# MB1-Hed-r1_0.net
KiCad netlist of a schematic drawn in Altium Designer
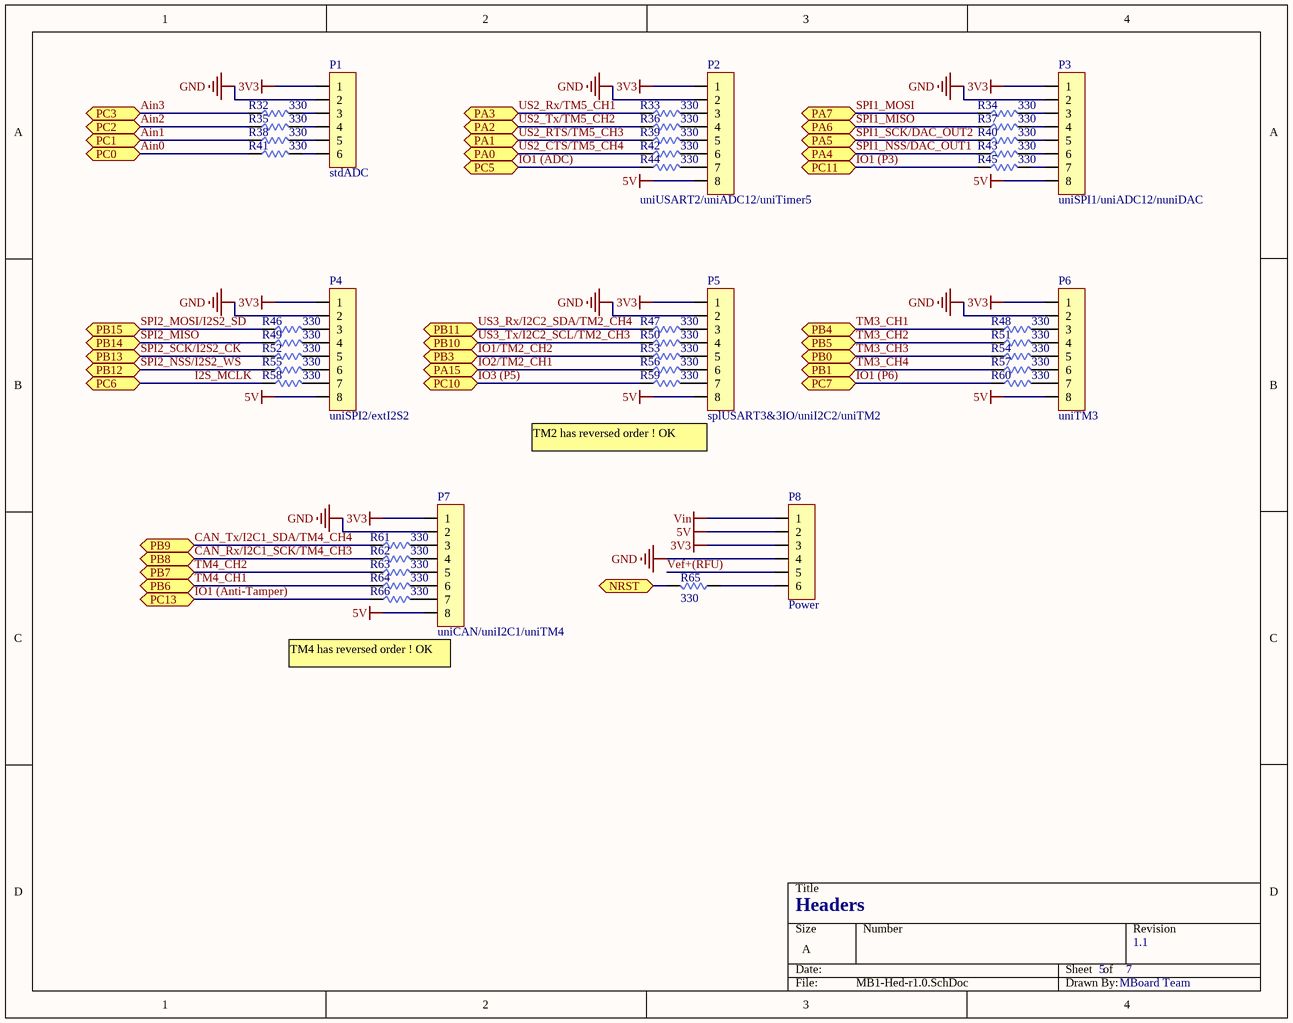
[diagram p0: MB1-Hed-r1.0.SchDoc]

(export (version "E")
  (design (tool "Eeschema 10.0.6"))
  (components
    (comp (ref "P1") (value "stdADC") (footprint "Hed6") (libsource (lib "MyLib") (part "Hed6")))
    (comp (ref "P2")
      (value "uniUSART2/uniADC12/uniTimer5")
      (footprint "Hed8")
      (libsource (lib "MyLib") (part "Hed8"))
    )
    (comp (ref "P3")
      (value "uniSPI1/uniADC12/nuniDAC")
      (footprint "Hed8")
      (libsource (lib "MyLib") (part "Hed8"))
    )
    (comp (ref "P4") (value "uniSPI2/extI2S2") (footprint "Hed8") (libsource (lib "MyLib") (part "Hed8")))
    (comp (ref "P5")
      (value "splUSART3&3IO/uniI2C2/uniTM2")
      (footprint "Hed8")
      (libsource (lib "MyLib") (part "Hed8"))
    )
    (comp (ref "P6") (value "uniTM3") (footprint "Hed8") (libsource (lib "MyLib") (part "Hed8")))
    (comp (ref "P7")
      (value "uniCAN/uniI2C1/uniTM4")
      (footprint "Hed8")
      (libsource (lib "MyLib") (part "Hed8"))
    )
    (comp (ref "P8") (value "Power") (footprint "Hed6") (libsource (lib "MyLib") (part "Hed6")))
    (comp (ref "R32")
      (value "330")
      (footprint "SM_0805_R")
      (description "Resistor")
      (fields (field (name "Comment") "R") (field (name "PUBLISHER") "Altium Limited"))
      (libsource (lib "HLib_schematic_lib") (part "R"))
    )
    (comp (ref "R33")
      (value "330")
      (footprint "SM_0805_R")
      (description "Resistor")
      (fields (field (name "Comment") "R") (field (name "PUBLISHER") "Altium Limited"))
      (libsource (lib "HLib_schematic_lib") (part "R"))
    )
    (comp (ref "R34")
      (value "330")
      (footprint "SM_0805_R")
      (description "Resistor")
      (fields (field (name "Comment") "R") (field (name "PUBLISHER") "Altium Limited"))
      (libsource (lib "HLib_schematic_lib") (part "R"))
    )
    (comp (ref "R35")
      (value "330")
      (footprint "SM_0805_R")
      (description "Resistor")
      (fields (field (name "Comment") "R") (field (name "PUBLISHER") "Altium Limited"))
      (libsource (lib "HLib_schematic_lib") (part "R"))
    )
    (comp (ref "R36")
      (value "330")
      (footprint "SM_0805_R")
      (description "Resistor")
      (fields (field (name "Comment") "R") (field (name "PUBLISHER") "Altium Limited"))
      (libsource (lib "HLib_schematic_lib") (part "R"))
    )
    (comp (ref "R37")
      (value "330")
      (footprint "SM_0805_R")
      (description "Resistor")
      (fields (field (name "Comment") "R") (field (name "PUBLISHER") "Altium Limited"))
      (libsource (lib "HLib_schematic_lib") (part "R"))
    )
    (comp (ref "R38")
      (value "330")
      (footprint "SM_0805_R")
      (description "Resistor")
      (fields (field (name "Comment") "R") (field (name "PUBLISHER") "Altium Limited"))
      (libsource (lib "HLib_schematic_lib") (part "R"))
    )
    (comp (ref "R39")
      (value "330")
      (footprint "SM_0805_R")
      (description "Resistor")
      (fields (field (name "Comment") "R") (field (name "PUBLISHER") "Altium Limited"))
      (libsource (lib "HLib_schematic_lib") (part "R"))
    )
    (comp (ref "R40")
      (value "330")
      (footprint "SM_0805_R")
      (description "Resistor")
      (fields (field (name "Comment") "R") (field (name "PUBLISHER") "Altium Limited"))
      (libsource (lib "HLib_schematic_lib") (part "R"))
    )
    (comp (ref "R41")
      (value "330")
      (footprint "SM_0805_R")
      (description "Resistor")
      (fields (field (name "Comment") "R") (field (name "PUBLISHER") "Altium Limited"))
      (libsource (lib "HLib_schematic_lib") (part "R"))
    )
    (comp (ref "R42")
      (value "330")
      (footprint "SM_0805_R")
      (description "Resistor")
      (fields (field (name "Comment") "R") (field (name "PUBLISHER") "Altium Limited"))
      (libsource (lib "HLib_schematic_lib") (part "R"))
    )
    (comp (ref "R43")
      (value "330")
      (footprint "SM_0805_R")
      (description "Resistor")
      (fields (field (name "Comment") "R") (field (name "PUBLISHER") "Altium Limited"))
      (libsource (lib "HLib_schematic_lib") (part "R"))
    )
    (comp (ref "R44")
      (value "330")
      (footprint "SM_0805_R")
      (description "Resistor")
      (fields (field (name "Comment") "R") (field (name "PUBLISHER") "Altium Limited"))
      (libsource (lib "HLib_schematic_lib") (part "R"))
    )
    (comp (ref "R45")
      (value "330")
      (footprint "SM_0805_R")
      (description "Resistor")
      (fields (field (name "Comment") "R") (field (name "PUBLISHER") "Altium Limited"))
      (libsource (lib "HLib_schematic_lib") (part "R"))
    )
    (comp (ref "R46")
      (value "330")
      (footprint "SM_0805_R")
      (description "Resistor")
      (fields (field (name "Comment") "R") (field (name "PUBLISHER") "Altium Limited"))
      (libsource (lib "HLib_schematic_lib") (part "R"))
    )
    (comp (ref "R47")
      (value "330")
      (footprint "SM_0805_R")
      (description "Resistor")
      (fields (field (name "Comment") "R") (field (name "PUBLISHER") "Altium Limited"))
      (libsource (lib "HLib_schematic_lib") (part "R"))
    )
    (comp (ref "R48")
      (value "330")
      (footprint "SM_0805_R")
      (description "Resistor")
      (fields (field (name "Comment") "R") (field (name "PUBLISHER") "Altium Limited"))
      (libsource (lib "HLib_schematic_lib") (part "R"))
    )
    (comp (ref "R49")
      (value "330")
      (footprint "SM_0805_R")
      (description "Resistor")
      (fields (field (name "Comment") "R") (field (name "PUBLISHER") "Altium Limited"))
      (libsource (lib "HLib_schematic_lib") (part "R"))
    )
    (comp (ref "R50")
      (value "330")
      (footprint "SM_0805_R")
      (description "Resistor")
      (fields (field (name "Comment") "R") (field (name "PUBLISHER") "Altium Limited"))
      (libsource (lib "HLib_schematic_lib") (part "R"))
    )
    (comp (ref "R51")
      (value "330")
      (footprint "SM_0805_R")
      (description "Resistor")
      (fields (field (name "Comment") "R") (field (name "PUBLISHER") "Altium Limited"))
      (libsource (lib "HLib_schematic_lib") (part "R"))
    )
    (comp (ref "R52")
      (value "330")
      (footprint "SM_0805_R")
      (description "Resistor")
      (fields (field (name "Comment") "R") (field (name "PUBLISHER") "Altium Limited"))
      (libsource (lib "HLib_schematic_lib") (part "R"))
    )
    (comp (ref "R53")
      (value "330")
      (footprint "SM_0805_R")
      (description "Resistor")
      (fields (field (name "Comment") "R") (field (name "PUBLISHER") "Altium Limited"))
      (libsource (lib "HLib_schematic_lib") (part "R"))
    )
    (comp (ref "R54")
      (value "330")
      (footprint "SM_0805_R")
      (description "Resistor")
      (fields (field (name "Comment") "R") (field (name "PUBLISHER") "Altium Limited"))
      (libsource (lib "HLib_schematic_lib") (part "R"))
    )
    (comp (ref "R55")
      (value "330")
      (footprint "SM_0805_R")
      (description "Resistor")
      (fields (field (name "Comment") "R") (field (name "PUBLISHER") "Altium Limited"))
      (libsource (lib "HLib_schematic_lib") (part "R"))
    )
    (comp (ref "R56")
      (value "330")
      (footprint "SM_0805_R")
      (description "Resistor")
      (fields (field (name "Comment") "R") (field (name "PUBLISHER") "Altium Limited"))
      (libsource (lib "HLib_schematic_lib") (part "R"))
    )
    (comp (ref "R57")
      (value "330")
      (footprint "SM_0805_R")
      (description "Resistor")
      (fields (field (name "Comment") "R") (field (name "PUBLISHER") "Altium Limited"))
      (libsource (lib "HLib_schematic_lib") (part "R"))
    )
    (comp (ref "R58")
      (value "330")
      (footprint "SM_0805_R")
      (description "Resistor")
      (fields (field (name "Comment") "R") (field (name "PUBLISHER") "Altium Limited"))
      (libsource (lib "HLib_schematic_lib") (part "R"))
    )
    (comp (ref "R59")
      (value "330")
      (footprint "SM_0805_R")
      (description "Resistor")
      (fields (field (name "Comment") "R") (field (name "PUBLISHER") "Altium Limited"))
      (libsource (lib "HLib_schematic_lib") (part "R"))
    )
    (comp (ref "R60")
      (value "330")
      (footprint "SM_0805_R")
      (description "Resistor")
      (fields (field (name "Comment") "R") (field (name "PUBLISHER") "Altium Limited"))
      (libsource (lib "HLib_schematic_lib") (part "R"))
    )
    (comp (ref "R61")
      (value "330")
      (footprint "SM_0805_R")
      (description "Resistor")
      (fields (field (name "Comment") "R") (field (name "PUBLISHER") "Altium Limited"))
      (libsource (lib "HLib_schematic_lib") (part "R"))
    )
    (comp (ref "R62")
      (value "330")
      (footprint "SM_0805_R")
      (description "Resistor")
      (fields (field (name "Comment") "R") (field (name "PUBLISHER") "Altium Limited"))
      (libsource (lib "HLib_schematic_lib") (part "R"))
    )
    (comp (ref "R63")
      (value "330")
      (footprint "SM_0805_R")
      (description "Resistor")
      (fields (field (name "Comment") "R") (field (name "PUBLISHER") "Altium Limited"))
      (libsource (lib "HLib_schematic_lib") (part "R"))
    )
    (comp (ref "R64")
      (value "330")
      (footprint "SM_0805_R")
      (description "Resistor")
      (fields (field (name "Comment") "R") (field (name "PUBLISHER") "Altium Limited"))
      (libsource (lib "HLib_schematic_lib") (part "R"))
    )
    (comp (ref "R65")
      (value "330")
      (footprint "SM_0805_R")
      (description "Resistor")
      (fields (field (name "Comment") "R") (field (name "PUBLISHER") "Altium Limited"))
      (libsource (lib "HLib_schematic_lib") (part "R"))
    )
    (comp (ref "R66")
      (value "330")
      (footprint "SM_0805_R")
      (description "Resistor")
      (fields (field (name "Comment") "R") (field (name "PUBLISHER") "Altium Limited"))
      (libsource (lib "HLib_schematic_lib") (part "R"))
    )
  )
  (nets
    (net (code "1") (name "/Ain0") (class "Default")
      (node (ref "R41") (pin "1") (pinfunction "1_1") (pintype "passive"))
    )
    (net (code "2") (name "/Ain1") (class "Default")
      (node (ref "R38") (pin "1") (pinfunction "1_1") (pintype "passive"))
    )
    (net (code "3") (name "/Ain2") (class "Default")
      (node (ref "R35") (pin "1") (pinfunction "1_1") (pintype "passive"))
    )
    (net (code "4") (name "/Ain3") (class "Default")
      (node (ref "R32") (pin "1") (pinfunction "1_1") (pintype "passive"))
    )
    (net (code "5") (name "/CAN_Rx{slash}I2C1_SCK{slash}TM4_CH3") (class "Default")
      (node (ref "R62") (pin "1") (pinfunction "1_1") (pintype "passive"))
    )
    (net (code "6") (name "/CAN_Tx{slash}I2C1_SDA{slash}TM4_CH4") (class "Default")
      (node (ref "R61") (pin "1") (pinfunction "1_1") (pintype "passive"))
    )
    (net (code "7") (name "/I2S_MCLK") (class "Default")
      (node (ref "R58") (pin "1") (pinfunction "1_1") (pintype "passive"))
    )
    (net (code "8") (name "/IO1 (ADC)") (class "Default")
      (node (ref "R44") (pin "1") (pinfunction "1_1") (pintype "passive"))
    )
    (net (code "9") (name "/IO1 (Anti-Tamper)") (class "Default")
      (node (ref "R66") (pin "1") (pinfunction "1_1") (pintype "passive"))
    )
    (net (code "10") (name "/IO1 (P3)") (class "Default")
      (node (ref "R45") (pin "1") (pinfunction "1_1") (pintype "passive"))
    )
    (net (code "11") (name "/IO1 (P6)") (class "Default")
      (node (ref "R60") (pin "1") (pinfunction "1_1") (pintype "passive"))
    )
    (net (code "12") (name "/IO1{slash}TM2_CH2") (class "Default")
      (node (ref "R53") (pin "1") (pinfunction "1_1") (pintype "passive"))
    )
    (net (code "13") (name "/IO2{slash}TM2_CH1") (class "Default")
      (node (ref "R56") (pin "1") (pinfunction "1_1") (pintype "passive"))
    )
    (net (code "14") (name "/IO3 (P5)") (class "Default")
      (node (ref "R59") (pin "1") (pinfunction "1_1") (pintype "passive"))
    )
    (net (code "15") (name "/NRST") (class "Default")
      (node (ref "R65") (pin "1") (pinfunction "1_1") (pintype "passive"))
    )
    (net (code "16") (name "/SPI1_MISO") (class "Default")
      (node (ref "R37") (pin "1") (pinfunction "1_1") (pintype "passive"))
    )
    (net (code "17") (name "/SPI1_MOSI") (class "Default")
      (node (ref "R34") (pin "1") (pinfunction "1_1") (pintype "passive"))
    )
    (net (code "18") (name "/SPI1_NSS{slash}DAC_OUT1") (class "Default")
      (node (ref "R43") (pin "1") (pinfunction "1_1") (pintype "passive"))
    )
    (net (code "19") (name "/SPI1_SCK{slash}DAC_OUT2") (class "Default")
      (node (ref "R40") (pin "1") (pinfunction "1_1") (pintype "passive"))
    )
    (net (code "20") (name "/SPI2_MISO") (class "Default")
      (node (ref "R49") (pin "1") (pinfunction "1_1") (pintype "passive"))
    )
    (net (code "21") (name "/SPI2_MOSI{slash}I2S2_SD") (class "Default")
      (node (ref "R46") (pin "1") (pinfunction "1_1") (pintype "passive"))
    )
    (net (code "22") (name "/SPI2_NSS{slash}I2S2_WS") (class "Default")
      (node (ref "R55") (pin "1") (pinfunction "1_1") (pintype "passive"))
    )
    (net (code "23") (name "/SPI2_SCK{slash}I2S2_CK") (class "Default")
      (node (ref "R52") (pin "1") (pinfunction "1_1") (pintype "passive"))
    )
    (net (code "24") (name "/TM3_CH1") (class "Default")
      (node (ref "R48") (pin "1") (pinfunction "1_1") (pintype "passive"))
    )
    (net (code "25") (name "/TM3_CH2") (class "Default")
      (node (ref "R51") (pin "1") (pinfunction "1_1") (pintype "passive"))
    )
    (net (code "26") (name "/TM3_CH3") (class "Default")
      (node (ref "R54") (pin "1") (pinfunction "1_1") (pintype "passive"))
    )
    (net (code "27") (name "/TM3_CH4") (class "Default")
      (node (ref "R57") (pin "1") (pinfunction "1_1") (pintype "passive"))
    )
    (net (code "28") (name "/TM4_CH1") (class "Default")
      (node (ref "R64") (pin "1") (pinfunction "1_1") (pintype "passive"))
    )
    (net (code "29") (name "/TM4_CH2") (class "Default")
      (node (ref "R63") (pin "1") (pinfunction "1_1") (pintype "passive"))
    )
    (net (code "30") (name "/US2_CTS{slash}TM5_CH4") (class "Default")
      (node (ref "R42") (pin "1") (pinfunction "1_1") (pintype "passive"))
    )
    (net (code "31") (name "/US2_RTS{slash}TM5_CH3") (class "Default")
      (node (ref "R39") (pin "1") (pinfunction "1_1") (pintype "passive"))
    )
    (net (code "32") (name "/US2_Rx{slash}TM5_CH1") (class "Default")
      (node (ref "R33") (pin "1") (pinfunction "1_1") (pintype "passive"))
    )
    (net (code "33") (name "/US2_Tx{slash}TM5_CH2") (class "Default")
      (node (ref "R36") (pin "1") (pinfunction "1_1") (pintype "passive"))
    )
    (net (code "34") (name "/US3_Rx{slash}I2C2_SDA{slash}TM2_CH4") (class "Default")
      (node (ref "R47") (pin "1") (pinfunction "1_1") (pintype "passive"))
    )
    (net (code "35") (name "/US3_Tx{slash}I2C2_SCL{slash}TM2_CH3") (class "Default")
      (node (ref "R50") (pin "1") (pinfunction "1_1") (pintype "passive"))
    )
    (net (code "36") (name "/Vef+(RFU)") (class "Default")
      (node (ref "P8") (pin "5") (pinfunction "5_5") (pintype "passive"))
    )
    (net (code "37") (name "3V3") (class "Default")
      (node (ref "P1") (pin "1") (pinfunction "1_1") (pintype "passive"))
      (node (ref "P2") (pin "1") (pinfunction "1_1") (pintype "passive"))
      (node (ref "P3") (pin "1") (pinfunction "1_1") (pintype "passive"))
      (node (ref "P4") (pin "1") (pinfunction "1_1") (pintype "passive"))
      (node (ref "P5") (pin "1") (pinfunction "1_1") (pintype "passive"))
      (node (ref "P6") (pin "1") (pinfunction "1_1") (pintype "passive"))
      (node (ref "P7") (pin "1") (pinfunction "1_1") (pintype "passive"))
      (node (ref "P8") (pin "3") (pinfunction "3_3") (pintype "passive"))
    )
    (net (code "38") (name "5V") (class "Default")
      (node (ref "P2") (pin "8") (pinfunction "8_8") (pintype "passive"))
      (node (ref "P3") (pin "8") (pinfunction "8_8") (pintype "passive"))
      (node (ref "P4") (pin "8") (pinfunction "8_8") (pintype "passive"))
      (node (ref "P5") (pin "8") (pinfunction "8_8") (pintype "passive"))
      (node (ref "P6") (pin "8") (pinfunction "8_8") (pintype "passive"))
      (node (ref "P7") (pin "8") (pinfunction "8_8") (pintype "passive"))
      (node (ref "P8") (pin "2") (pinfunction "2_2") (pintype "passive"))
    )
    (net (code "39") (name "GND") (class "Default")
      (node (ref "P1") (pin "2") (pinfunction "2_2") (pintype "passive"))
      (node (ref "P2") (pin "2") (pinfunction "2_2") (pintype "passive"))
      (node (ref "P3") (pin "2") (pinfunction "2_2") (pintype "passive"))
      (node (ref "P4") (pin "2") (pinfunction "2_2") (pintype "passive"))
      (node (ref "P5") (pin "2") (pinfunction "2_2") (pintype "passive"))
      (node (ref "P6") (pin "2") (pinfunction "2_2") (pintype "passive"))
      (node (ref "P7") (pin "2") (pinfunction "2_2") (pintype "passive"))
      (node (ref "P8") (pin "4") (pinfunction "4_4") (pintype "passive"))
    )
    (net (code "40") (name "Net-(P1-Pad3)") (class "Default")
      (node (ref "P1") (pin "3") (pinfunction "3_3") (pintype "passive"))
      (node (ref "R32") (pin "2") (pinfunction "2_2") (pintype "passive"))
    )
    (net (code "41") (name "Net-(P1-Pad4)") (class "Default")
      (node (ref "P1") (pin "4") (pinfunction "4_4") (pintype "passive"))
      (node (ref "R35") (pin "2") (pinfunction "2_2") (pintype "passive"))
    )
    (net (code "42") (name "Net-(P1-Pad5)") (class "Default")
      (node (ref "P1") (pin "5") (pinfunction "5_5") (pintype "passive"))
      (node (ref "R38") (pin "2") (pinfunction "2_2") (pintype "passive"))
    )
    (net (code "43") (name "Net-(P1-Pad6)") (class "Default")
      (node (ref "P1") (pin "6") (pinfunction "6_6") (pintype "passive"))
      (node (ref "R41") (pin "2") (pinfunction "2_2") (pintype "passive"))
    )
    (net (code "44") (name "Net-(P2-Pad3)") (class "Default")
      (node (ref "P2") (pin "3") (pinfunction "3_3") (pintype "passive"))
      (node (ref "R33") (pin "2") (pinfunction "2_2") (pintype "passive"))
    )
    (net (code "45") (name "Net-(P2-Pad4)") (class "Default")
      (node (ref "P2") (pin "4") (pinfunction "4_4") (pintype "passive"))
      (node (ref "R36") (pin "2") (pinfunction "2_2") (pintype "passive"))
    )
    (net (code "46") (name "Net-(P2-Pad5)") (class "Default")
      (node (ref "P2") (pin "5") (pinfunction "5_5") (pintype "passive"))
      (node (ref "R39") (pin "2") (pinfunction "2_2") (pintype "passive"))
    )
    (net (code "47") (name "Net-(P2-Pad6)") (class "Default")
      (node (ref "P2") (pin "6") (pinfunction "6_6") (pintype "passive"))
      (node (ref "R42") (pin "2") (pinfunction "2_2") (pintype "passive"))
    )
    (net (code "48") (name "Net-(P2-Pad7)") (class "Default")
      (node (ref "P2") (pin "7") (pinfunction "7_7") (pintype "passive"))
      (node (ref "R44") (pin "2") (pinfunction "2_2") (pintype "passive"))
    )
    (net (code "49") (name "Net-(P3-Pad3)") (class "Default")
      (node (ref "P3") (pin "3") (pinfunction "3_3") (pintype "passive"))
      (node (ref "R34") (pin "2") (pinfunction "2_2") (pintype "passive"))
    )
    (net (code "50") (name "Net-(P3-Pad4)") (class "Default")
      (node (ref "P3") (pin "4") (pinfunction "4_4") (pintype "passive"))
      (node (ref "R37") (pin "2") (pinfunction "2_2") (pintype "passive"))
    )
    (net (code "51") (name "Net-(P3-Pad5)") (class "Default")
      (node (ref "P3") (pin "5") (pinfunction "5_5") (pintype "passive"))
      (node (ref "R40") (pin "2") (pinfunction "2_2") (pintype "passive"))
    )
    (net (code "52") (name "Net-(P3-Pad6)") (class "Default")
      (node (ref "P3") (pin "6") (pinfunction "6_6") (pintype "passive"))
      (node (ref "R43") (pin "2") (pinfunction "2_2") (pintype "passive"))
    )
    (net (code "53") (name "Net-(P3-Pad7)") (class "Default")
      (node (ref "P3") (pin "7") (pinfunction "7_7") (pintype "passive"))
      (node (ref "R45") (pin "2") (pinfunction "2_2") (pintype "passive"))
    )
    (net (code "54") (name "Net-(P4-Pad3)") (class "Default")
      (node (ref "P4") (pin "3") (pinfunction "3_3") (pintype "passive"))
      (node (ref "R46") (pin "2") (pinfunction "2_2") (pintype "passive"))
    )
    (net (code "55") (name "Net-(P4-Pad4)") (class "Default")
      (node (ref "P4") (pin "4") (pinfunction "4_4") (pintype "passive"))
      (node (ref "R49") (pin "2") (pinfunction "2_2") (pintype "passive"))
    )
    (net (code "56") (name "Net-(P4-Pad5)") (class "Default")
      (node (ref "P4") (pin "5") (pinfunction "5_5") (pintype "passive"))
      (node (ref "R52") (pin "2") (pinfunction "2_2") (pintype "passive"))
    )
    (net (code "57") (name "Net-(P4-Pad6)") (class "Default")
      (node (ref "P4") (pin "6") (pinfunction "6_6") (pintype "passive"))
      (node (ref "R55") (pin "2") (pinfunction "2_2") (pintype "passive"))
    )
    (net (code "58") (name "Net-(P4-Pad7)") (class "Default")
      (node (ref "P4") (pin "7") (pinfunction "7_7") (pintype "passive"))
      (node (ref "R58") (pin "2") (pinfunction "2_2") (pintype "passive"))
    )
    (net (code "59") (name "Net-(P5-Pad3)") (class "Default")
      (node (ref "P5") (pin "3") (pinfunction "3_3") (pintype "passive"))
      (node (ref "R47") (pin "2") (pinfunction "2_2") (pintype "passive"))
    )
    (net (code "60") (name "Net-(P5-Pad4)") (class "Default")
      (node (ref "P5") (pin "4") (pinfunction "4_4") (pintype "passive"))
      (node (ref "R50") (pin "2") (pinfunction "2_2") (pintype "passive"))
    )
    (net (code "61") (name "Net-(P5-Pad5)") (class "Default")
      (node (ref "P5") (pin "5") (pinfunction "5_5") (pintype "passive"))
      (node (ref "R53") (pin "2") (pinfunction "2_2") (pintype "passive"))
    )
    (net (code "62") (name "Net-(P5-Pad6)") (class "Default")
      (node (ref "P5") (pin "6") (pinfunction "6_6") (pintype "passive"))
      (node (ref "R56") (pin "2") (pinfunction "2_2") (pintype "passive"))
    )
    (net (code "63") (name "Net-(P5-Pad7)") (class "Default")
      (node (ref "P5") (pin "7") (pinfunction "7_7") (pintype "passive"))
      (node (ref "R59") (pin "2") (pinfunction "2_2") (pintype "passive"))
    )
    (net (code "64") (name "Net-(P6-Pad3)") (class "Default")
      (node (ref "P6") (pin "3") (pinfunction "3_3") (pintype "passive"))
      (node (ref "R48") (pin "2") (pinfunction "2_2") (pintype "passive"))
    )
    (net (code "65") (name "Net-(P6-Pad4)") (class "Default")
      (node (ref "P6") (pin "4") (pinfunction "4_4") (pintype "passive"))
      (node (ref "R51") (pin "2") (pinfunction "2_2") (pintype "passive"))
    )
    (net (code "66") (name "Net-(P6-Pad5)") (class "Default")
      (node (ref "P6") (pin "5") (pinfunction "5_5") (pintype "passive"))
      (node (ref "R54") (pin "2") (pinfunction "2_2") (pintype "passive"))
    )
    (net (code "67") (name "Net-(P6-Pad6)") (class "Default")
      (node (ref "P6") (pin "6") (pinfunction "6_6") (pintype "passive"))
      (node (ref "R57") (pin "2") (pinfunction "2_2") (pintype "passive"))
    )
    (net (code "68") (name "Net-(P6-Pad7)") (class "Default")
      (node (ref "P6") (pin "7") (pinfunction "7_7") (pintype "passive"))
      (node (ref "R60") (pin "2") (pinfunction "2_2") (pintype "passive"))
    )
    (net (code "69") (name "Net-(P7-Pad3)") (class "Default")
      (node (ref "P7") (pin "3") (pinfunction "3_3") (pintype "passive"))
      (node (ref "R61") (pin "2") (pinfunction "2_2") (pintype "passive"))
    )
    (net (code "70") (name "Net-(P7-Pad4)") (class "Default")
      (node (ref "P7") (pin "4") (pinfunction "4_4") (pintype "passive"))
      (node (ref "R62") (pin "2") (pinfunction "2_2") (pintype "passive"))
    )
    (net (code "71") (name "Net-(P7-Pad5)") (class "Default")
      (node (ref "P7") (pin "5") (pinfunction "5_5") (pintype "passive"))
      (node (ref "R63") (pin "2") (pinfunction "2_2") (pintype "passive"))
    )
    (net (code "72") (name "Net-(P7-Pad6)") (class "Default")
      (node (ref "P7") (pin "6") (pinfunction "6_6") (pintype "passive"))
      (node (ref "R64") (pin "2") (pinfunction "2_2") (pintype "passive"))
    )
    (net (code "73") (name "Net-(P7-Pad7)") (class "Default")
      (node (ref "P7") (pin "7") (pinfunction "7_7") (pintype "passive"))
      (node (ref "R66") (pin "2") (pinfunction "2_2") (pintype "passive"))
    )
    (net (code "74") (name "Net-(P8-Pad6)") (class "Default")
      (node (ref "P8") (pin "6") (pinfunction "6_6") (pintype "passive"))
      (node (ref "R65") (pin "2") (pinfunction "2_2") (pintype "passive"))
    )
    (net (code "75") (name "Vin") (class "Default")
      (node (ref "P8") (pin "1") (pinfunction "1_1") (pintype "passive"))
    )
  )
)
